# DAC_PLL.net
KiCad netlist of a schematic drawn in Altium Designer
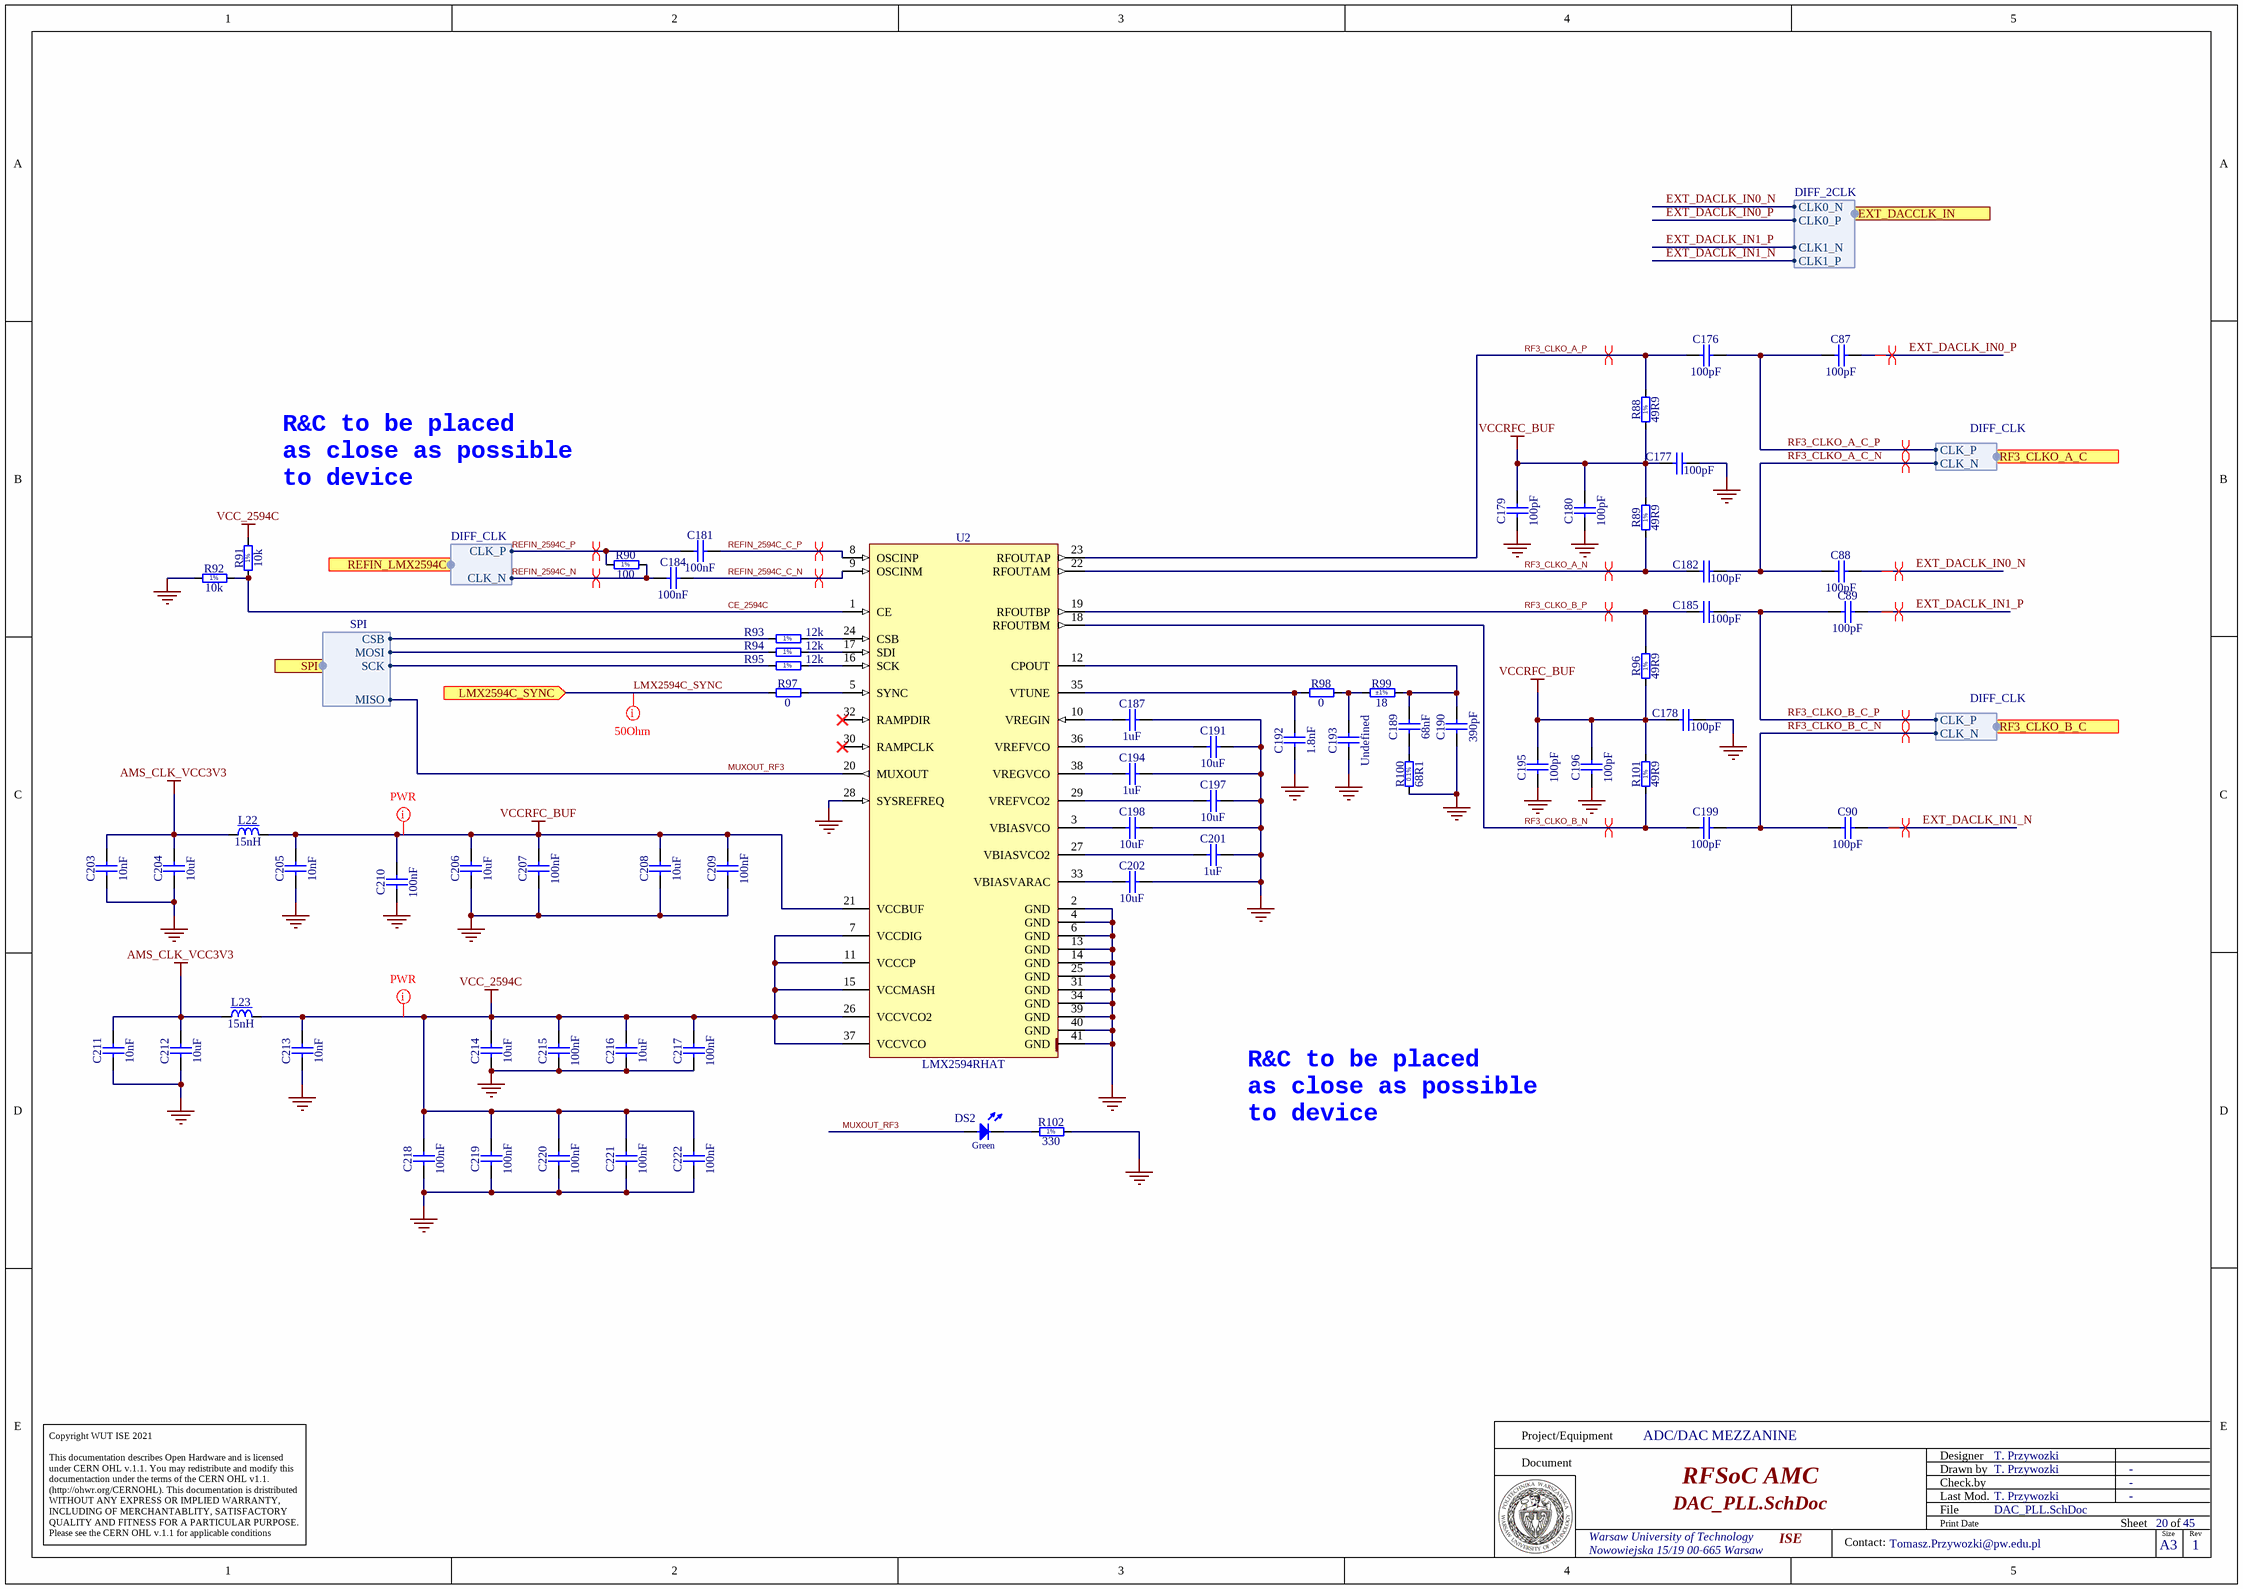
[diagram p0: DAC_PLL.SchDoc]

(export (version "E")
  (design (tool "Eeschema 10.0.6"))
  (components
    (comp (ref "C87")
      (value "100pF")
      (footprint "CAPC1005X55N")
      (description "Non-polarised capacitor")
      (fields
        (field (name "PART NUMBER") "CC0402_100PF_25V_5%_C0G_KEMET_HiQ-CBR")
        (field (name "VOLTAGE") "25V")
        (field (name "AUTHOR") "CERN DEM MR")
      )
      (libsource (lib "Capacitors") (part "Capacitor - non polarized"))
    )
    (comp (ref "C88")
      (value "100pF")
      (footprint "CAPC1005X55N")
      (description "Non-polarised capacitor")
      (fields
        (field (name "PART NUMBER") "CC0402_100PF_25V_5%_C0G_KEMET_HiQ-CBR")
        (field (name "VOLTAGE") "25V")
        (field (name "AUTHOR") "CERN DEM MR")
      )
      (libsource (lib "Capacitors") (part "Capacitor - non polarized"))
    )
    (comp (ref "C89")
      (value "100pF")
      (footprint "CAPC1005X55N")
      (description "Non-polarised capacitor")
      (fields
        (field (name "PART NUMBER") "CC0402_100PF_25V_5%_C0G_KEMET_HiQ-CBR")
        (field (name "VOLTAGE") "25V")
        (field (name "AUTHOR") "CERN DEM MR")
      )
      (libsource (lib "Capacitors") (part "Capacitor - non polarized"))
    )
    (comp (ref "C90")
      (value "100pF")
      (footprint "CAPC1005X55N")
      (description "Non-polarised capacitor")
      (fields
        (field (name "PART NUMBER") "CC0402_100PF_25V_5%_C0G_KEMET_HiQ-CBR")
        (field (name "VOLTAGE") "25V")
        (field (name "AUTHOR") "CERN DEM MR")
      )
      (libsource (lib "Capacitors") (part "Capacitor - non polarized"))
    )
    (comp (ref "C176")
      (value "100pF")
      (footprint "CAPC1005X55N")
      (description "Non-polarised capacitor")
      (fields
        (field (name "PART NUMBER") "CC0402_100PF_25V_5%_C0G_KEMET_HiQ-CBR")
        (field (name "VOLTAGE") "25V")
        (field (name "AUTHOR") "CERN DEM MR")
      )
      (libsource (lib "Capacitors") (part "Capacitor - non polarized"))
    )
    (comp (ref "C177")
      (value "100pF")
      (footprint "CAPC1005X55N")
      (description "Non-polarised capacitor")
      (fields
        (field (name "PART NUMBER") "CC0402_100PF_25V_5%_C0G_KEMET_HiQ-CBR")
        (field (name "VOLTAGE") "25V")
        (field (name "AUTHOR") "CERN DEM MR")
      )
      (libsource (lib "Capacitors") (part "Capacitor - non polarized"))
    )
    (comp (ref "C178")
      (value "100pF")
      (footprint "CAPC1005X55N")
      (description "Non-polarised capacitor")
      (fields
        (field (name "PART NUMBER") "CC0402_100PF_25V_5%_C0G_KEMET_HiQ-CBR")
        (field (name "VOLTAGE") "25V")
        (field (name "AUTHOR") "CERN DEM MR")
      )
      (libsource (lib "Capacitors") (part "Capacitor - non polarized"))
    )
    (comp (ref "C179")
      (value "100pF")
      (footprint "CAPC1005X55N")
      (description "Non-polarised capacitor")
      (fields
        (field (name "PART NUMBER") "CC0402_100PF_25V_5%_C0G_KEMET_HiQ-CBR")
        (field (name "VOLTAGE") "25V")
        (field (name "AUTHOR") "CERN DEM MR")
      )
      (libsource (lib "Capacitors") (part "Capacitor - non polarized"))
    )
    (comp (ref "C180")
      (value "100pF")
      (footprint "CAPC1005X55N")
      (description "Non-polarised capacitor")
      (fields
        (field (name "PART NUMBER") "CC0402_100PF_25V_5%_C0G_KEMET_HiQ-CBR")
        (field (name "VOLTAGE") "25V")
        (field (name "AUTHOR") "CERN DEM MR")
      )
      (libsource (lib "Capacitors") (part "Capacitor - non polarized"))
    )
    (comp (ref "C181")
      (value "100nF")
      (footprint "CAPC1005X55N")
      (description "Non-polarised capacitor")
      (fields
        (field (name "PART NUMBER") "CC0402_100NF_25V_10%_X7R_YUDEN_TMK105B7104KVHF")
        (field (name "VOLTAGE") "25V")
        (field (name "AUTHOR") "CERN DEM JLC")
      )
      (libsource (lib "Capacitors") (part "Capacitor - non polarized"))
    )
    (comp (ref "C182")
      (value "100pF")
      (footprint "CAPC1005X55N")
      (description "Non-polarised capacitor")
      (fields
        (field (name "PART NUMBER") "CC0402_100PF_25V_5%_C0G_KEMET_HiQ-CBR")
        (field (name "VOLTAGE") "25V")
        (field (name "AUTHOR") "CERN DEM MR")
      )
      (libsource (lib "Capacitors") (part "Capacitor - non polarized"))
    )
    (comp (ref "C184")
      (value "100nF")
      (footprint "CAPC1005X55N")
      (description "Non-polarised capacitor")
      (fields
        (field (name "PART NUMBER") "CC0402_100NF_25V_10%_X7R_YUDEN_TMK105B7104KVHF")
        (field (name "VOLTAGE") "25V")
        (field (name "AUTHOR") "CERN DEM JLC")
      )
      (libsource (lib "Capacitors") (part "Capacitor - non polarized"))
    )
    (comp (ref "C185")
      (value "100pF")
      (footprint "CAPC1005X55N")
      (description "Non-polarised capacitor")
      (fields
        (field (name "PART NUMBER") "CC0402_100PF_25V_5%_C0G_KEMET_HiQ-CBR")
        (field (name "VOLTAGE") "25V")
        (field (name "AUTHOR") "CERN DEM MR")
      )
      (libsource (lib "Capacitors") (part "Capacitor - non polarized"))
    )
    (comp (ref "C187")
      (value "1uF")
      (footprint "CAPC1005X55N")
      (description "Non-polarised capacitor")
      (fields
        (field (name "PART NUMBER") "CC0402_1UF_16V_10%_X5R")
        (field (name "VOLTAGE") "16V")
        (field (name "AUTHOR") "CERN DEM JLC")
      )
      (libsource (lib "Capacitors") (part "Capacitor - non polarized"))
    )
    (comp (ref "C189")
      (value "68nF")
      (footprint "CAPC1005X55N")
      (description "Non-polarised capacitor")
      (fields
        (field (name "PART NUMBER") "CC0402_68NF_16V_10%_X7R")
        (field (name "VOLTAGE") "16V")
        (field (name "AUTHOR") "CERN DEM JLC")
      )
      (libsource (lib "Capacitors") (part "Capacitor - non polarized"))
    )
    (comp (ref "C190")
      (value "390pF")
      (footprint "CAPC1608X87N")
      (description "Non-polarised capacitor")
      (fields
        (field (name "PART NUMBER") "CC0603_390PF_50V_5%_NP0")
        (field (name "VOLTAGE") "50V")
        (field (name "AUTHOR") "CERN DEM JLC")
      )
      (libsource (lib "Capacitors") (part "Capacitor - non polarized"))
    )
    (comp (ref "C191")
      (value "10uF")
      (footprint "CAPC1608X80N")
      (description "Non-polarised capacitor")
      (fields
        (field (name "PART NUMBER") "CC0603_10UF_10V_10%_X5R")
        (field (name "VOLTAGE") "10V")
        (field (name "AUTHOR") "CERN DEM JLC")
      )
      (libsource (lib "Capacitors") (part "Capacitor - non polarized"))
    )
    (comp (ref "C192")
      (value "1.8nF")
      (footprint "CAPC1608X87N")
      (description "Non-polarised capacitor")
      (fields
        (field (name "PART NUMBER") "CC0603_1.8NF_50V_5%_X7R")
        (field (name "VOLTAGE") "50V")
        (field (name "AUTHOR") "CERN DEM JLC")
      )
      (libsource (lib "Capacitors") (part "Capacitor - non polarized"))
    )
    (comp (ref "C193")
      (value "Undefined")
      (footprint "CAPC1005X55N")
      (description "Non-polarised capacitor")
      (fields (field (name "PART NUMBER") "CC0402_NO-VALUE") (field (name "AUTHOR") "CERN DEM JLC"))
      (libsource (lib "Capacitors") (part "Capacitor - non polarized"))
    )
    (comp (ref "C194")
      (value "1uF")
      (footprint "CAPC1005X55N")
      (description "Non-polarised capacitor")
      (fields
        (field (name "PART NUMBER") "CC0402_1UF_16V_10%_X5R")
        (field (name "VOLTAGE") "16V")
        (field (name "AUTHOR") "CERN DEM JLC")
      )
      (libsource (lib "Capacitors") (part "Capacitor - non polarized"))
    )
    (comp (ref "C195")
      (value "100pF")
      (footprint "CAPC1005X55N")
      (description "Non-polarised capacitor")
      (fields
        (field (name "PART NUMBER") "CC0402_100PF_25V_5%_C0G_KEMET_HiQ-CBR")
        (field (name "VOLTAGE") "25V")
        (field (name "AUTHOR") "CERN DEM MR")
      )
      (libsource (lib "Capacitors") (part "Capacitor - non polarized"))
    )
    (comp (ref "C196")
      (value "100pF")
      (footprint "CAPC1005X55N")
      (description "Non-polarised capacitor")
      (fields
        (field (name "PART NUMBER") "CC0402_100PF_25V_5%_C0G_KEMET_HiQ-CBR")
        (field (name "VOLTAGE") "25V")
        (field (name "AUTHOR") "CERN DEM MR")
      )
      (libsource (lib "Capacitors") (part "Capacitor - non polarized"))
    )
    (comp (ref "C197")
      (value "10uF")
      (footprint "CAPC1608X80N")
      (description "Non-polarised capacitor")
      (fields
        (field (name "PART NUMBER") "CC0603_10UF_10V_10%_X5R")
        (field (name "VOLTAGE") "10V")
        (field (name "AUTHOR") "CERN DEM JLC")
      )
      (libsource (lib "Capacitors") (part "Capacitor - non polarized"))
    )
    (comp (ref "C198")
      (value "10uF")
      (footprint "CAPC1608X80N")
      (description "Non-polarised capacitor")
      (fields
        (field (name "PART NUMBER") "CC0603_10UF_10V_10%_X5R")
        (field (name "VOLTAGE") "10V")
        (field (name "AUTHOR") "CERN DEM JLC")
      )
      (libsource (lib "Capacitors") (part "Capacitor - non polarized"))
    )
    (comp (ref "C199")
      (value "100pF")
      (footprint "CAPC1005X55N")
      (description "Non-polarised capacitor")
      (fields
        (field (name "PART NUMBER") "CC0402_100PF_25V_5%_C0G_KEMET_HiQ-CBR")
        (field (name "VOLTAGE") "25V")
        (field (name "AUTHOR") "CERN DEM MR")
      )
      (libsource (lib "Capacitors") (part "Capacitor - non polarized"))
    )
    (comp (ref "C201")
      (value "1uF")
      (footprint "CAPC1005X55N")
      (description "Non-polarised capacitor")
      (fields
        (field (name "PART NUMBER") "CC0402_1UF_16V_10%_X5R")
        (field (name "VOLTAGE") "16V")
        (field (name "AUTHOR") "CERN DEM JLC")
      )
      (libsource (lib "Capacitors") (part "Capacitor - non polarized"))
    )
    (comp (ref "C202")
      (value "10uF")
      (footprint "CAPC1608X80N")
      (description "Non-polarised capacitor")
      (fields
        (field (name "PART NUMBER") "CC0603_10UF_10V_10%_X5R")
        (field (name "VOLTAGE") "10V")
        (field (name "AUTHOR") "CERN DEM JLC")
      )
      (libsource (lib "Capacitors") (part "Capacitor - non polarized"))
    )
    (comp (ref "C203")
      (value "10nF")
      (footprint "CAPC1005X55N")
      (description "Non-polarised capacitor")
      (fields
        (field (name "PART NUMBER") "CC0402_10NF_16V_10%_X7R")
        (field (name "VOLTAGE") "16V")
        (field (name "AUTHOR") "CERN DEM JLC")
      )
      (libsource (lib "Capacitors") (part "Capacitor - non polarized"))
    )
    (comp (ref "C204")
      (value "10uF")
      (footprint "CAPC1608X80N")
      (description "Non-polarised capacitor")
      (fields
        (field (name "PART NUMBER") "CC0603_10UF_10V_10%_X5R")
        (field (name "VOLTAGE") "10V")
        (field (name "AUTHOR") "CERN DEM JLC")
      )
      (libsource (lib "Capacitors") (part "Capacitor - non polarized"))
    )
    (comp (ref "C205")
      (value "10nF")
      (footprint "CAPC1005X55N")
      (description "Non-polarised capacitor")
      (fields
        (field (name "PART NUMBER") "CC0402_10NF_16V_10%_X7R")
        (field (name "VOLTAGE") "16V")
        (field (name "AUTHOR") "CERN DEM JLC")
      )
      (libsource (lib "Capacitors") (part "Capacitor - non polarized"))
    )
    (comp (ref "C206")
      (value "10uF")
      (footprint "CAPC1608X80N")
      (description "Non-polarised capacitor")
      (fields
        (field (name "PART NUMBER") "CC0603_10UF_10V_10%_X5R")
        (field (name "VOLTAGE") "10V")
        (field (name "AUTHOR") "CERN DEM JLC")
      )
      (libsource (lib "Capacitors") (part "Capacitor - non polarized"))
    )
    (comp (ref "C207")
      (value "100nF")
      (footprint "CAPC1005X55N")
      (description "Non-polarised capacitor")
      (fields
        (field (name "PART NUMBER") "CC0402_100NF_25V_10%_X7R_YUDEN_TMK105B7104KVHF")
        (field (name "VOLTAGE") "25V")
        (field (name "AUTHOR") "CERN DEM JLC")
      )
      (libsource (lib "Capacitors") (part "Capacitor - non polarized"))
    )
    (comp (ref "C208")
      (value "10uF")
      (footprint "CAPC1608X80N")
      (description "Non-polarised capacitor")
      (fields
        (field (name "PART NUMBER") "CC0603_10UF_10V_10%_X5R")
        (field (name "VOLTAGE") "10V")
        (field (name "AUTHOR") "CERN DEM JLC")
      )
      (libsource (lib "Capacitors") (part "Capacitor - non polarized"))
    )
    (comp (ref "C209")
      (value "100nF")
      (footprint "CAPC1005X55N")
      (description "Non-polarised capacitor")
      (fields
        (field (name "PART NUMBER") "CC0402_100NF_25V_10%_X7R_YUDEN_TMK105B7104KVHF")
        (field (name "VOLTAGE") "25V")
        (field (name "AUTHOR") "CERN DEM JLC")
      )
      (libsource (lib "Capacitors") (part "Capacitor - non polarized"))
    )
    (comp (ref "C210")
      (value "100nF")
      (footprint "CAPC1005X55N")
      (description "Non-polarised capacitor")
      (fields
        (field (name "PART NUMBER") "CC0402_100NF_25V_10%_X7R_YUDEN_TMK105B7104KVHF")
        (field (name "VOLTAGE") "25V")
        (field (name "AUTHOR") "CERN DEM JLC")
      )
      (libsource (lib "Capacitors") (part "Capacitor - non polarized"))
    )
    (comp (ref "C211")
      (value "10nF")
      (footprint "CAPC1005X55N")
      (description "Non-polarised capacitor")
      (fields
        (field (name "PART NUMBER") "CC0402_10NF_16V_10%_X7R")
        (field (name "VOLTAGE") "16V")
        (field (name "AUTHOR") "CERN DEM JLC")
      )
      (libsource (lib "Capacitors") (part "Capacitor - non polarized"))
    )
    (comp (ref "C212")
      (value "10uF")
      (footprint "CAPC1608X80N")
      (description "Non-polarised capacitor")
      (fields
        (field (name "PART NUMBER") "CC0603_10UF_10V_10%_X5R")
        (field (name "VOLTAGE") "10V")
        (field (name "AUTHOR") "CERN DEM JLC")
      )
      (libsource (lib "Capacitors") (part "Capacitor - non polarized"))
    )
    (comp (ref "C213")
      (value "10nF")
      (footprint "CAPC1005X55N")
      (description "Non-polarised capacitor")
      (fields
        (field (name "PART NUMBER") "CC0402_10NF_16V_10%_X7R")
        (field (name "VOLTAGE") "16V")
        (field (name "AUTHOR") "CERN DEM JLC")
      )
      (libsource (lib "Capacitors") (part "Capacitor - non polarized"))
    )
    (comp (ref "C214")
      (value "10uF")
      (footprint "CAPC1608X80N")
      (description "Non-polarised capacitor")
      (fields
        (field (name "PART NUMBER") "CC0603_10UF_10V_10%_X5R")
        (field (name "VOLTAGE") "10V")
        (field (name "AUTHOR") "CERN DEM JLC")
      )
      (libsource (lib "Capacitors") (part "Capacitor - non polarized"))
    )
    (comp (ref "C215")
      (value "100nF")
      (footprint "CAPC1005X55N")
      (description "Non-polarised capacitor")
      (fields
        (field (name "PART NUMBER") "CC0402_100NF_25V_10%_X7R_YUDEN_TMK105B7104KVHF")
        (field (name "VOLTAGE") "25V")
        (field (name "AUTHOR") "CERN DEM JLC")
      )
      (libsource (lib "Capacitors") (part "Capacitor - non polarized"))
    )
    (comp (ref "C216")
      (value "10uF")
      (footprint "CAPC1608X80N")
      (description "Non-polarised capacitor")
      (fields
        (field (name "PART NUMBER") "CC0603_10UF_10V_10%_X5R")
        (field (name "VOLTAGE") "10V")
        (field (name "AUTHOR") "CERN DEM JLC")
      )
      (libsource (lib "Capacitors") (part "Capacitor - non polarized"))
    )
    (comp (ref "C217")
      (value "100nF")
      (footprint "CAPC1005X55N")
      (description "Non-polarised capacitor")
      (fields
        (field (name "PART NUMBER") "CC0402_100NF_25V_10%_X7R_YUDEN_TMK105B7104KVHF")
        (field (name "VOLTAGE") "25V")
        (field (name "AUTHOR") "CERN DEM JLC")
      )
      (libsource (lib "Capacitors") (part "Capacitor - non polarized"))
    )
    (comp (ref "C218")
      (value "100nF")
      (footprint "CAPC1005X55N")
      (description "Non-polarised capacitor")
      (fields
        (field (name "PART NUMBER") "CC0402_100NF_25V_10%_X7R_YUDEN_TMK105B7104KVHF")
        (field (name "VOLTAGE") "25V")
        (field (name "AUTHOR") "CERN DEM JLC")
      )
      (libsource (lib "Capacitors") (part "Capacitor - non polarized"))
    )
    (comp (ref "C219")
      (value "100nF")
      (footprint "CAPC1005X55N")
      (description "Non-polarised capacitor")
      (fields
        (field (name "PART NUMBER") "CC0402_100NF_25V_10%_X7R_YUDEN_TMK105B7104KVHF")
        (field (name "VOLTAGE") "25V")
        (field (name "AUTHOR") "CERN DEM JLC")
      )
      (libsource (lib "Capacitors") (part "Capacitor - non polarized"))
    )
    (comp (ref "C220")
      (value "100nF")
      (footprint "CAPC1005X55N")
      (description "Non-polarised capacitor")
      (fields
        (field (name "PART NUMBER") "CC0402_100NF_25V_10%_X7R_YUDEN_TMK105B7104KVHF")
        (field (name "VOLTAGE") "25V")
        (field (name "AUTHOR") "CERN DEM JLC")
      )
      (libsource (lib "Capacitors") (part "Capacitor - non polarized"))
    )
    (comp (ref "C221")
      (value "100nF")
      (footprint "CAPC1005X55N")
      (description "Non-polarised capacitor")
      (fields
        (field (name "PART NUMBER") "CC0402_100NF_25V_10%_X7R_YUDEN_TMK105B7104KVHF")
        (field (name "VOLTAGE") "25V")
        (field (name "AUTHOR") "CERN DEM JLC")
      )
      (libsource (lib "Capacitors") (part "Capacitor - non polarized"))
    )
    (comp (ref "C222")
      (value "100nF")
      (footprint "CAPC1005X55N")
      (description "Non-polarised capacitor")
      (fields
        (field (name "PART NUMBER") "CC0402_100NF_25V_10%_X7R_YUDEN_TMK105B7104KVHF")
        (field (name "VOLTAGE") "25V")
        (field (name "AUTHOR") "CERN DEM JLC")
      )
      (libsource (lib "Capacitors") (part "Capacitor - non polarized"))
    )
    (comp (ref "DS2")
      (value "Green")
      (footprint "LED_OSRAM_LGL29K")
      (description "LED Green 1C 2A")
      (fields
        (field (name "PART NUMBER") "LED_OSRAM_LG L29K-G2J1-24-Z")
        (field (name "MANUFACTURER") "OSRAM")
        (field (name "AUTHOR") "CERN DEM JLC")
      )
      (libsource (lib "ICs And Semiconductors") (part "LED Green 1C 2A"))
    )
    (comp (ref "L22")
      (value "15nH")
      (footprint "IND_COILCRAFT_0402DC")
      (description "Inductor With Core")
      (fields
        (field (name "PART NUMBER") "IND0402_15NH_2%_COILCRAFT_0402DC")
        (field (name "POWER") "1A")
        (field (name "AUTHOR") "CERN DEM JLC")
      )
      (libsource (lib "Inductors & Transformers") (part "Inductor With Magnetic core"))
    )
    (comp (ref "L23")
      (value "15nH")
      (footprint "IND_COILCRAFT_0402DC")
      (description "Inductor With Core")
      (fields
        (field (name "PART NUMBER") "IND0402_15NH_2%_COILCRAFT_0402DC")
        (field (name "POWER") "1A")
        (field (name "AUTHOR") "CERN DEM JLC")
      )
      (libsource (lib "Inductors & Transformers") (part "Inductor With Magnetic core"))
    )
    (comp (ref "R88")
      (value "49R9")
      (footprint "RESC1005X40N")
      (description "Resistor - 1%")
      (fields
        (field (name "PART NUMBER") "R0402_49R9_1%_0.0625W_100PPM")
        (field (name "POWER") "0.0625W")
        (field (name "AUTHOR") "CERN DEM JLC")
      )
      (libsource (lib "Resistors") (part "Resistor - 1%"))
    )
    (comp (ref "R89")
      (value "49R9")
      (footprint "RESC1005X40N")
      (description "Resistor - 1%")
      (fields
        (field (name "PART NUMBER") "R0402_49R9_1%_0.0625W_100PPM")
        (field (name "POWER") "0.0625W")
        (field (name "AUTHOR") "CERN DEM JLC")
      )
      (libsource (lib "Resistors") (part "Resistor - 1%"))
    )
    (comp (ref "R90")
      (value "100")
      (footprint "RESC1005X40N")
      (description "Resistor - 1%")
      (fields
        (field (name "PART NUMBER") "R0402_100R_1%_0.1W_100PPM")
        (field (name "POWER") "0.1W")
        (field (name "AUTHOR") "CERN DEM JLC")
      )
      (libsource (lib "Resistors") (part "Resistor - 1%"))
    )
    (comp (ref "R91")
      (value "10k")
      (footprint "RESC1005X40N")
      (description "Resistor - 1%")
      (fields
        (field (name "PART NUMBER") "R0402_10K_1%_0.0625W_100PPM")
        (field (name "POWER") "0.0625W")
        (field (name "AUTHOR") "CERN DEM JLC")
      )
      (libsource (lib "Resistors") (part "Resistor - 1%"))
    )
    (comp (ref "R92")
      (value "10k")
      (footprint "RESC1005X40N")
      (description "Resistor - 1%")
      (fields
        (field (name "PART NUMBER") "R0402_10K_1%_0.0625W_100PPM")
        (field (name "POWER") "0.0625W")
        (field (name "AUTHOR") "CERN DEM JLC")
      )
      (libsource (lib "Resistors") (part "Resistor - 1%"))
    )
    (comp (ref "R93")
      (value "12k")
      (footprint "RESC1005X40N")
      (description "Resistor - 1%")
      (fields
        (field (name "PART NUMBER") "R0402_12K_1%_0.0625W_100PPM")
        (field (name "POWER") "0.0625W")
        (field (name "AUTHOR") "CERN DEM JLC")
      )
      (libsource (lib "Resistors") (part "Resistor - 1%"))
    )
    (comp (ref "R94")
      (value "12k")
      (footprint "RESC1005X40N")
      (description "Resistor - 1%")
      (fields
        (field (name "PART NUMBER") "R0402_12K_1%_0.0625W_100PPM")
        (field (name "POWER") "0.0625W")
        (field (name "AUTHOR") "CERN DEM JLC")
      )
      (libsource (lib "Resistors") (part "Resistor - 1%"))
    )
    (comp (ref "R95")
      (value "12k")
      (footprint "RESC1005X40N")
      (description "Resistor - 1%")
      (fields
        (field (name "PART NUMBER") "R0402_12K_1%_0.0625W_100PPM")
        (field (name "POWER") "0.0625W")
        (field (name "AUTHOR") "CERN DEM JLC")
      )
      (libsource (lib "Resistors") (part "Resistor - 1%"))
    )
    (comp (ref "R96")
      (value "49R9")
      (footprint "RESC1005X40N")
      (description "Resistor - 1%")
      (fields
        (field (name "PART NUMBER") "R0402_49R9_1%_0.0625W_100PPM")
        (field (name "POWER") "0.0625W")
        (field (name "AUTHOR") "CERN DEM JLC")
      )
      (libsource (lib "Resistors") (part "Resistor - 1%"))
    )
    (comp (ref "R97")
      (value "0")
      (footprint "RESC1005X40N")
      (description "Resistor")
      (fields
        (field (name "PART NUMBER") "R0402_0R_JUMPER")
        (field (name "MANUFACTURER") "GENERIC")
        (field (name "AUTHOR") "CERN DEM JLC")
      )
      (libsource (lib "Resistors") (part "Resistor"))
    )
    (comp (ref "R98")
      (value "0")
      (footprint "RESC1005X40N")
      (description "Resistor")
      (fields
        (field (name "PART NUMBER") "R0402_0R_JUMPER")
        (field (name "MANUFACTURER") "GENERIC")
        (field (name "AUTHOR") "CERN DEM JLC")
      )
      (libsource (lib "Resistors") (part "Resistor"))
    )
    (comp (ref "R99")
      (value "18")
      (footprint "RESC1005X40N")
      (description "Resistor - 1%")
      (fields
        (field (name "TOLERANCE") "±1%")
        (field (name "PART NUMBER") "R0402_18R_1%_0.0625W_100PPM")
        (field (name "POWER") "0.0625W")
        (field (name "AUTHOR") "CERN DEM JLC")
      )
      (libsource (lib "Resistors") (part "Resistor - 1%"))
    )
    (comp (ref "R100")
      (value "68R1")
      (footprint "RESC1608X55N")
      (description "Resistor - 0.1%")
      (fields
        (field (name "PART NUMBER") "R0603_68R1_0.1%_0.063W_10PPM")
        (field (name "POWER") "0.063W")
        (field (name "AUTHOR") "CERN DEM JLC")
      )
      (libsource (lib "Resistors") (part "Resistor - 0.1%"))
    )
    (comp (ref "R101")
      (value "49R9")
      (footprint "RESC1005X40N")
      (description "Resistor - 1%")
      (fields
        (field (name "PART NUMBER") "R0402_49R9_1%_0.0625W_100PPM")
        (field (name "POWER") "0.0625W")
        (field (name "AUTHOR") "CERN DEM JLC")
      )
      (libsource (lib "Resistors") (part "Resistor - 1%"))
    )
    (comp (ref "R102")
      (value "330")
      (footprint "RESC1005X40N")
      (description "Resistor - 1%")
      (fields
        (field (name "TOLERANCE") "±1%")
        (field (name "POWER") "0.0625W")
        (field (name "AUTHOR") "CERN DEM JLC")
      )
      (libsource (lib "Resistors") (part "Resistor - 1%"))
    )
    (comp (ref "U2")
      (value "LMX2594RHAT")
      (footprint "QFN50P600X600X100-41N-S460")
      (description "15GHz Wideband PLLatinum RF Synthesizer with Phase Synchronization and JESD204B Support")
      (fields (field (name "MANUFACTURER") "TEXAS INSTRUMENTS") (field (name "AUTHOR") "CERN DEM JLC"))
      (libsource (lib "ICs And Semiconductors") (part "LMX2594"))
    )
  )
  (nets
    (net (code "4") (name "/CE_2594C") (class "Default")
      (node (ref "R91") (pin "1") (pinfunction "1_1") (pintype "passive"))
      (node (ref "R92") (pin "2") (pinfunction "2_2") (pintype "passive"))
      (node (ref "U2") (pin "1") (pinfunction "CE_1") (pintype "input"))
    )
    (net (code "5") (name "/CSB") (class "Default")
      (node (ref "R93") (pin "2") (pinfunction "2_2") (pintype "passive"))
    )
    (net (code "6") (name "/EXT_DACLK_IN0_N") (class "Default")
      (node (ref "C88") (pin "2") (pinfunction "2_2") (pintype "passive"))
    )
    (net (code "7") (name "/EXT_DACLK_IN0_P") (class "Default")
      (node (ref "C87") (pin "2") (pinfunction "2_2") (pintype "passive"))
    )
    (net (code "8") (name "/EXT_DACLK_IN1_N") (class "Default")
      (node (ref "C90") (pin "2") (pinfunction "2_2") (pintype "passive"))
    )
    (net (code "9") (name "/EXT_DACLK_IN1_P") (class "Default")
      (node (ref "C89") (pin "2") (pinfunction "2_2") (pintype "passive"))
    )
    (net (code "10") (name "/LMX2594C_SYNC") (class "Default")
      (node (ref "R97") (pin "1") (pinfunction "1_1") (pintype "passive"))
    )
    (net (code "11") (name "/MOSI") (class "Default")
      (node (ref "R94") (pin "2") (pinfunction "2_2") (pintype "passive"))
    )
    (net (code "12") (name "/MUXOUT_RF3") (class "Default")
      (node (ref "DS2") (pin "2") (pinfunction "A_2") (pintype "passive"))
      (node (ref "U2") (pin "20") (pinfunction "MUXOUT_20") (pintype "output"))
    )
    (net (code "13") (name "/REFIN_2594C_C_N") (class "Default")
      (node (ref "C184") (pin "2") (pinfunction "2_2") (pintype "passive"))
      (node (ref "U2") (pin "9") (pinfunction "OSCINM_9") (pintype "input"))
    )
    (net (code "14") (name "/REFIN_2594C_C_P") (class "Default")
      (node (ref "C181") (pin "2") (pinfunction "2_2") (pintype "passive"))
      (node (ref "U2") (pin "8") (pinfunction "OSCINP_8") (pintype "input"))
    )
    (net (code "15") (name "/REFIN_2594C_N") (class "Default")
      (node (ref "C184") (pin "1") (pinfunction "1_1") (pintype "passive"))
      (node (ref "R90") (pin "2") (pinfunction "2_2") (pintype "passive"))
    )
    (net (code "16") (name "/REFIN_2594C_P") (class "Default")
      (node (ref "C181") (pin "1") (pinfunction "1_1") (pintype "passive"))
      (node (ref "R90") (pin "1") (pinfunction "1_1") (pintype "passive"))
    )
    (net (code "17") (name "/RF3_CLKO_A_C_N") (class "Default")
      (node (ref "C182") (pin "2") (pinfunction "2_2") (pintype "passive"))
      (node (ref "C88") (pin "1") (pinfunction "1_1") (pintype "passive"))
    )
    (net (code "18") (name "/RF3_CLKO_A_C_P") (class "Default")
      (node (ref "C176") (pin "2") (pinfunction "2_2") (pintype "passive"))
      (node (ref "C87") (pin "1") (pinfunction "1_1") (pintype "passive"))
    )
    (net (code "19") (name "/RF3_CLKO_A_N") (class "Default")
      (node (ref "C182") (pin "1") (pinfunction "1_1") (pintype "passive"))
      (node (ref "R89") (pin "1") (pinfunction "1_1") (pintype "passive"))
      (node (ref "U2") (pin "22") (pinfunction "RFOUTAM_22") (pintype "output"))
    )
    (net (code "20") (name "/RF3_CLKO_A_P") (class "Default")
      (node (ref "C176") (pin "1") (pinfunction "1_1") (pintype "passive"))
      (node (ref "R88") (pin "2") (pinfunction "2_2") (pintype "passive"))
      (node (ref "U2") (pin "23") (pinfunction "RFOUTAP_23") (pintype "output"))
    )
    (net (code "21") (name "/RF3_CLKO_B_C_N") (class "Default")
      (node (ref "C199") (pin "2") (pinfunction "2_2") (pintype "passive"))
      (node (ref "C90") (pin "1") (pinfunction "1_1") (pintype "passive"))
    )
    (net (code "22") (name "/RF3_CLKO_B_C_P") (class "Default")
      (node (ref "C185") (pin "2") (pinfunction "2_2") (pintype "passive"))
      (node (ref "C89") (pin "1") (pinfunction "1_1") (pintype "passive"))
    )
    (net (code "23") (name "/RF3_CLKO_B_N") (class "Default")
      (node (ref "C199") (pin "1") (pinfunction "1_1") (pintype "passive"))
      (node (ref "R101") (pin "1") (pinfunction "1_1") (pintype "passive"))
      (node (ref "U2") (pin "18") (pinfunction "RFOUTBM_18") (pintype "output"))
    )
    (net (code "24") (name "/RF3_CLKO_B_P") (class "Default")
      (node (ref "C185") (pin "1") (pinfunction "1_1") (pintype "passive"))
      (node (ref "R96") (pin "2") (pinfunction "2_2") (pintype "passive"))
      (node (ref "U2") (pin "19") (pinfunction "RFOUTBP_19") (pintype "output"))
    )
    (net (code "25") (name "/SCK") (class "Default")
      (node (ref "R95") (pin "2") (pinfunction "2_2") (pintype "passive"))
    )
    (net (code "29") (name "AMS_CLK_VCC3V3") (class "Default")
      (node (ref "C203") (pin "2") (pinfunction "2_2") (pintype "passive"))
      (node (ref "C204") (pin "2") (pinfunction "2_2") (pintype "passive"))
      (node (ref "C211") (pin "2") (pinfunction "2_2") (pintype "passive"))
      (node (ref "C212") (pin "2") (pinfunction "2_2") (pintype "passive"))
      (node (ref "L22") (pin "1") (pinfunction "1_1") (pintype "passive"))
      (node (ref "L23") (pin "1") (pinfunction "1_1") (pintype "passive"))
    )
    (net (code "30") (name "GND") (class "Default")
      (node (ref "C177") (pin "2") (pinfunction "2_2") (pintype "passive"))
      (node (ref "C178") (pin "2") (pinfunction "2_2") (pintype "passive"))
      (node (ref "C179") (pin "1") (pinfunction "1_1") (pintype "passive"))
      (node (ref "C180") (pin "1") (pinfunction "1_1") (pintype "passive"))
      (node (ref "C187") (pin "1") (pinfunction "1_1") (pintype "passive"))
      (node (ref "C190") (pin "1") (pinfunction "1_1") (pintype "passive"))
      (node (ref "C191") (pin "1") (pinfunction "1_1") (pintype "passive"))
      (node (ref "C192") (pin "1") (pinfunction "1_1") (pintype "passive"))
      (node (ref "C193") (pin "1") (pinfunction "1_1") (pintype "passive"))
      (node (ref "C194") (pin "1") (pinfunction "1_1") (pintype "passive"))
      (node (ref "C195") (pin "1") (pinfunction "1_1") (pintype "passive"))
      (node (ref "C196") (pin "1") (pinfunction "1_1") (pintype "passive"))
      (node (ref "C197") (pin "1") (pinfunction "1_1") (pintype "passive"))
      (node (ref "C198") (pin "1") (pinfunction "1_1") (pintype "passive"))
      (node (ref "C201") (pin "1") (pinfunction "1_1") (pintype "passive"))
      (node (ref "C202") (pin "1") (pinfunction "1_1") (pintype "passive"))
      (node (ref "C203") (pin "1") (pinfunction "1_1") (pintype "passive"))
      (node (ref "C204") (pin "1") (pinfunction "1_1") (pintype "passive"))
      (node (ref "C205") (pin "1") (pinfunction "1_1") (pintype "passive"))
      (node (ref "C206") (pin "1") (pinfunction "1_1") (pintype "passive"))
      (node (ref "C207") (pin "1") (pinfunction "1_1") (pintype "passive"))
      (node (ref "C208") (pin "1") (pinfunction "1_1") (pintype "passive"))
      (node (ref "C209") (pin "1") (pinfunction "1_1") (pintype "passive"))
      (node (ref "C210") (pin "1") (pinfunction "1_1") (pintype "passive"))
      (node (ref "C211") (pin "1") (pinfunction "1_1") (pintype "passive"))
      (node (ref "C212") (pin "1") (pinfunction "1_1") (pintype "passive"))
      (node (ref "C213") (pin "1") (pinfunction "1_1") (pintype "passive"))
      (node (ref "C214") (pin "1") (pinfunction "1_1") (pintype "passive"))
      (node (ref "C215") (pin "1") (pinfunction "1_1") (pintype "passive"))
      (node (ref "C216") (pin "1") (pinfunction "1_1") (pintype "passive"))
      (node (ref "C217") (pin "1") (pinfunction "1_1") (pintype "passive"))
      (node (ref "C218") (pin "1") (pinfunction "1_1") (pintype "passive"))
      (node (ref "C219") (pin "1") (pinfunction "1_1") (pintype "passive"))
      (node (ref "C220") (pin "1") (pinfunction "1_1") (pintype "passive"))
      (node (ref "C221") (pin "1") (pinfunction "1_1") (pintype "passive"))
      (node (ref "C222") (pin "1") (pinfunction "1_1") (pintype "passive"))
      (node (ref "R100") (pin "1") (pinfunction "1_1") (pintype "passive"))
      (node (ref "R102") (pin "2") (pinfunction "2_2") (pintype "passive"))
      (node (ref "R92") (pin "1") (pinfunction "1_1") (pintype "passive"))
      (node (ref "U2") (pin "13") (pinfunction "GND_13") (pintype "power_in"))
      (node (ref "U2") (pin "14") (pinfunction "GND_14") (pintype "power_in"))
      (node (ref "U2") (pin "2") (pinfunction "GND_2") (pintype "power_in"))
      (node (ref "U2") (pin "25") (pinfunction "GND_25") (pintype "power_in"))
      (node (ref "U2") (pin "28") (pinfunction "SYSREFREQ_28") (pintype "input"))
      (node (ref "U2") (pin "31") (pinfunction "GND_31") (pintype "power_in"))
      (node (ref "U2") (pin "34") (pinfunction "GND_34") (pintype "power_in"))
      (node (ref "U2") (pin "39") (pinfunction "GND_39") (pintype "power_in"))
      (node (ref "U2") (pin "4") (pinfunction "GND_4") (pintype "power_in"))
      (node (ref "U2") (pin "40") (pinfunction "GND_40") (pintype "power_in"))
      (node (ref "U2") (pin "41") (pinfunction "GND_41") (pintype "power_in"))
      (node (ref "U2") (pin "6") (pinfunction "GND_6") (pintype "power_in"))
    )
    (net (code "31") (name "Net-(C189-Pad1)") (class "Default")
      (node (ref "C189") (pin "1") (pinfunction "1_1") (pintype "passive"))
      (node (ref "R100") (pin "2") (pinfunction "2_2") (pintype "passive"))
    )
    (net (code "32") (name "Net-(C193-Pad2)") (class "Default")
      (node (ref "C193") (pin "2") (pinfunction "2_2") (pintype "passive"))
      (node (ref "R98") (pin "2") (pinfunction "2_2") (pintype "passive"))
      (node (ref "R99") (pin "1") (pinfunction "1_1") (pintype "passive"))
    )
    (net (code "33") (name "Net-(DS2-C)") (class "Default")
      (node (ref "DS2") (pin "1") (pinfunction "C_1") (pintype "passive"))
      (node (ref "R102") (pin "1") (pinfunction "1_1") (pintype "passive"))
    )
    (net (code "34") (name "Net-(U2-CPOUT)") (class "Default")
      (node (ref "C189") (pin "2") (pinfunction "2_2") (pintype "passive"))
      (node (ref "C190") (pin "2") (pinfunction "2_2") (pintype "passive"))
      (node (ref "R99") (pin "2") (pinfunction "2_2") (pintype "passive"))
      (node (ref "U2") (pin "12") (pinfunction "CPOUT_12") (pintype "passive"))
    )
    (net (code "35") (name "Net-(U2-CSB)") (class "Default")
      (node (ref "R93") (pin "1") (pinfunction "1_1") (pintype "passive"))
      (node (ref "U2") (pin "24") (pinfunction "CSB_24") (pintype "input"))
    )
    (net (code "36") (name "Net-(U2-SCK)") (class "Default")
      (node (ref "R95") (pin "1") (pinfunction "1_1") (pintype "passive"))
      (node (ref "U2") (pin "16") (pinfunction "SCK_16") (pintype "input"))
    )
    (net (code "37") (name "Net-(U2-SDI)") (class "Default")
      (node (ref "R94") (pin "1") (pinfunction "1_1") (pintype "passive"))
      (node (ref "U2") (pin "17") (pinfunction "SDI_17") (pintype "input"))
    )
    (net (code "38") (name "Net-(U2-SYNC)") (class "Default")
      (node (ref "R97") (pin "2") (pinfunction "2_2") (pintype "passive"))
      (node (ref "U2") (pin "5") (pinfunction "SYNC_5") (pintype "input"))
    )
    (net (code "39") (name "Net-(U2-VBIASVARAC)") (class "Default")
      (node (ref "C202") (pin "2") (pinfunction "2_2") (pintype "passive"))
      (node (ref "U2") (pin "33") (pinfunction "VBIASVARAC_33") (pintype "passive"))
    )
    (net (code "40") (name "Net-(U2-VBIASVCO)") (class "Default")
      (node (ref "C198") (pin "2") (pinfunction "2_2") (pintype "passive"))
      (node (ref "U2") (pin "3") (pinfunction "VBIASVCO_3") (pintype "passive"))
    )
    (net (code "41") (name "Net-(U2-VBIASVCO2)") (class "Default")
      (node (ref "C201") (pin "2") (pinfunction "2_2") (pintype "passive"))
      (node (ref "U2") (pin "27") (pinfunction "VBIASVCO2_27") (pintype "passive"))
    )
    (net (code "42") (name "Net-(U2-VREFVCO)") (class "Default")
      (node (ref "C191") (pin "2") (pinfunction "2_2") (pintype "passive"))
      (node (ref "U2") (pin "36") (pinfunction "VREFVCO_36") (pintype "passive"))
    )
    (net (code "43") (name "Net-(U2-VREFVCO2)") (class "Default")
      (node (ref "C197") (pin "2") (pinfunction "2_2") (pintype "passive"))
      (node (ref "U2") (pin "29") (pinfunction "VREFVCO2_29") (pintype "passive"))
    )
    (net (code "44") (name "Net-(U2-VREGIN)") (class "Default")
      (node (ref "C187") (pin "2") (pinfunction "2_2") (pintype "passive"))
      (node (ref "U2") (pin "10") (pinfunction "VREGIN_10") (pintype "input"))
    )
    (net (code "45") (name "Net-(U2-VREGVCO)") (class "Default")
      (node (ref "C194") (pin "2") (pinfunction "2_2") (pintype "passive"))
      (node (ref "U2") (pin "38") (pinfunction "VREGVCO_38") (pintype "passive"))
    )
    (net (code "46") (name "Net-(U2-VTUNE)") (class "Default")
      (node (ref "C192") (pin "2") (pinfunction "2_2") (pintype "passive"))
      (node (ref "R98") (pin "1") (pinfunction "1_1") (pintype "passive"))
      (node (ref "U2") (pin "35") (pinfunction "VTUNE_35") (pintype "passive"))
    )
    (net (code "47") (name "VCCRFC_BUF") (class "Default")
      (node (ref "C177") (pin "1") (pinfunction "1_1") (pintype "passive"))
      (node (ref "C178") (pin "1") (pinfunction "1_1") (pintype "passive"))
      (node (ref "C179") (pin "2") (pinfunction "2_2") (pintype "passive"))
      (node (ref "C180") (pin "2") (pinfunction "2_2") (pintype "passive"))
      (node (ref "C195") (pin "2") (pinfunction "2_2") (pintype "passive"))
      (node (ref "C196") (pin "2") (pinfunction "2_2") (pintype "passive"))
      (node (ref "C205") (pin "2") (pinfunction "2_2") (pintype "passive"))
      (node (ref "C206") (pin "2") (pinfunction "2_2") (pintype "passive"))
      (node (ref "C207") (pin "2") (pinfunction "2_2") (pintype "passive"))
      (node (ref "C208") (pin "2") (pinfunction "2_2") (pintype "passive"))
      (node (ref "C209") (pin "2") (pinfunction "2_2") (pintype "passive"))
      (node (ref "C210") (pin "2") (pinfunction "2_2") (pintype "passive"))
      (node (ref "L22") (pin "2") (pinfunction "2_2") (pintype "passive"))
      (node (ref "R101") (pin "2") (pinfunction "2_2") (pintype "passive"))
      (node (ref "R88") (pin "1") (pinfunction "1_1") (pintype "passive"))
      (node (ref "R89") (pin "2") (pinfunction "2_2") (pintype "passive"))
      (node (ref "R96") (pin "1") (pinfunction "1_1") (pintype "passive"))
      (node (ref "U2") (pin "21") (pinfunction "VCCBUF_21") (pintype "power_in"))
    )
    (net (code "48") (name "VCC_2594C") (class "Default")
      (node (ref "C213") (pin "2") (pinfunction "2_2") (pintype "passive"))
      (node (ref "C214") (pin "2") (pinfunction "2_2") (pintype "passive"))
      (node (ref "C215") (pin "2") (pinfunction "2_2") (pintype "passive"))
      (node (ref "C216") (pin "2") (pinfunction "2_2") (pintype "passive"))
      (node (ref "C217") (pin "2") (pinfunction "2_2") (pintype "passive"))
      (node (ref "C218") (pin "2") (pinfunction "2_2") (pintype "passive"))
      (node (ref "C219") (pin "2") (pinfunction "2_2") (pintype "passive"))
      (node (ref "C220") (pin "2") (pinfunction "2_2") (pintype "passive"))
      (node (ref "C221") (pin "2") (pinfunction "2_2") (pintype "passive"))
      (node (ref "C222") (pin "2") (pinfunction "2_2") (pintype "passive"))
      (node (ref "L23") (pin "2") (pinfunction "2_2") (pintype "passive"))
      (node (ref "R91") (pin "2") (pinfunction "2_2") (pintype "passive"))
      (node (ref "U2") (pin "11") (pinfunction "VCCCP_11") (pintype "power_in"))
      (node (ref "U2") (pin "15") (pinfunction "VCCMASH_15") (pintype "power_in"))
      (node (ref "U2") (pin "26") (pinfunction "VCCVCO2_26") (pintype "power_in"))
      (node (ref "U2") (pin "37") (pinfunction "VCCVCO_37") (pintype "power_in"))
      (node (ref "U2") (pin "7") (pinfunction "VCCDIG_7") (pintype "power_in"))
    )
    (net (code "49") (name "unconnected-(U2-RAMPCLK-Pad30)") (class "Default")
      (node (ref "U2") (pin "30") (pinfunction "RAMPCLK_30") (pintype "input+no_connect"))
    )
    (net (code "50") (name "unconnected-(U2-RAMPDIR-Pad32)") (class "Default")
      (node (ref "U2") (pin "32") (pinfunction "RAMPDIR_32") (pintype "input+no_connect"))
    )
  )
)
